# machnguon.net
KiCad netlist of a schematic drawn in Altium Designer
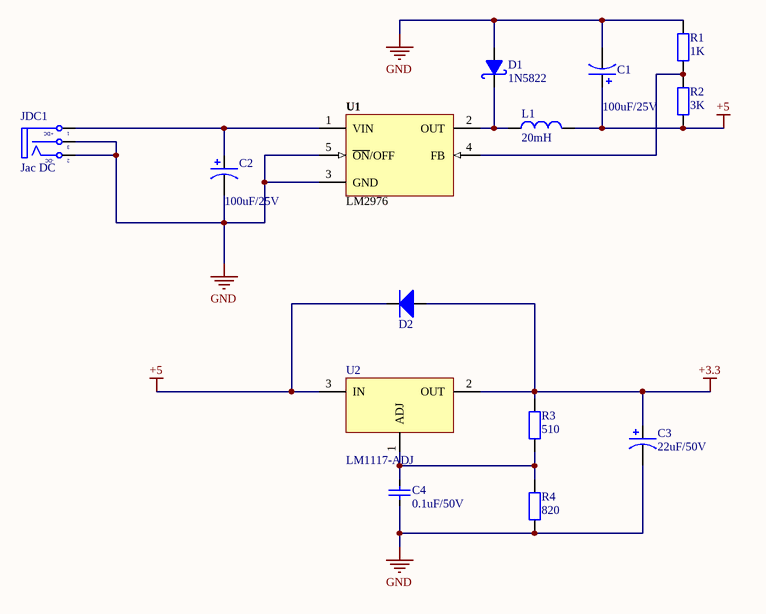
[diagram p0: machnguon.SchDoc]

(export (version "E")
  (design (tool "Eeschema 10.0.6"))
  (components
    (comp (ref "C1")
      (value "100uF/25V")
      (footprint "C3MM")
      (description "Polarized Capacitor (Axial)")
      (fields (field (name "PUBLISHER") "Altium Limited"))
      (libsource (lib "My Library") (part "Cap Pol"))
    )
    (comp (ref "C2")
      (value "100uF/25V")
      (footprint "C3MM")
      (description "Polarized Capacitor (Axial)")
      (fields (field (name "PUBLISHER") "Altium Limited"))
      (libsource (lib "My Library") (part "Cap Pol"))
    )
    (comp (ref "C3")
      (value "22uF/50V")
      (footprint "C3MM")
      (description "Polarized Capacitor (Axial)")
      (fields (field (name "PUBLISHER") "Altium Limited"))
      (libsource (lib "My Library") (part "Cap Pol"))
    )
    (comp (ref "C4")
      (value "0.1uF/50V")
      (footprint "CAP_0805")
      (description "Capacitor")
      (fields (field (name "PUBLISHER") "Altium Limited"))
      (libsource (lib "My Library") (part "CapSMD"))
    )
    (comp (ref "D1")
      (value "1N5822")
      (footprint "SMA")
      (description "Schottky Rectifiers")
      (libsource (lib "My Library") (part "1N5822"))
    )
    (comp (ref "D2")
      (value "Diode SMD")
      (footprint "DIO-SMD-106")
      (description "Default Diode")
      (fields (field (name "PUBLISHER") "Altium Limited"))
      (libsource (lib "My Library") (part "Diode SMD"))
    )
    (comp (ref "JDC1")
      (value "Jac DC")
      (footprint "DC-IN")
      (description "Jac DC input")
      (libsource (lib "My Library") (part "DCIN"))
    )
    (comp (ref "L1")
      (value "20mH")
      (footprint "L-SMD-M-7.3x4.5")
      (description "Inductor")
      (libsource (lib "My Library") (part "Inductor"))
    )
    (comp (ref "R1")
      (value "1K")
      (footprint "RES-SMD-0805")
      (description "Resistor SMD")
      (fields
        (field (name "MANUFACTURER") "Generic Components")
        (field (name "PUBLISHER") "Altium Hobart Technology Centre")
      )
      (libsource (lib "My Library") (part "Resistor - SMD"))
    )
    (comp (ref "R2")
      (value "3K")
      (footprint "RES-SMD-0805")
      (description "Resistor SMD")
      (fields
        (field (name "MANUFACTURER") "Generic Components")
        (field (name "PUBLISHER") "Altium Hobart Technology Centre")
      )
      (libsource (lib "My Library") (part "Resistor - SMD"))
    )
    (comp (ref "R3")
      (value "510")
      (footprint "RES-SMD-0805")
      (description "Resistor SMD")
      (fields
        (field (name "MANUFACTURER") "Generic Components")
        (field (name "PUBLISHER") "Altium Hobart Technology Centre")
      )
      (libsource (lib "My Library") (part "Resistor - SMD"))
    )
    (comp (ref "R4")
      (value "820")
      (footprint "RES-SMD-0805")
      (description "Resistor SMD")
      (fields
        (field (name "MANUFACTURER") "Generic Components")
        (field (name "PUBLISHER") "Altium Hobart Technology Centre")
      )
      (libsource (lib "My Library") (part "Resistor - SMD"))
    )
    (comp (ref "U1") (value "LM2976") (footprint "TO263") (libsource (lib "My Library") (part "LM2596")))
    (comp (ref "U2")
      (value "LM1117-ADJ")
      (footprint "LM1117-SOP")
      (description "800mA Low-Dropout Linear Regulator")
      (fields (field (name "CREATOR") "Nguyen Ba Bien"))
      (libsource (lib "My Library") (part "LM1117-ADJ"))
    )
  )
  (nets
    (net (code "1") (name "+3.3") (class "Default")
      (node (ref "C3") (pin "1") (pinfunction "1_1") (pintype "passive"))
      (node (ref "D2") (pin "1") (pinfunction "A_1") (pintype "passive"))
      (node (ref "R3") (pin "1") (pinfunction "1_1") (pintype "passive"))
      (node (ref "U2") (pin "2") (pinfunction "OUT_2") (pintype "passive"))
    )
    (net (code "2") (name "+5") (class "Default")
      (node (ref "C1") (pin "1") (pinfunction "1_1") (pintype "passive"))
      (node (ref "D2") (pin "2") (pinfunction "K_2") (pintype "passive"))
      (node (ref "L1") (pin "2") (pinfunction "2_2") (pintype "passive"))
      (node (ref "R2") (pin "2") (pinfunction "2_2") (pintype "passive"))
      (node (ref "U2") (pin "3") (pinfunction "IN_3") (pintype "passive"))
    )
    (net (code "3") (name "GND") (class "Default")
      (node (ref "C1") (pin "2") (pinfunction "2_2") (pintype "passive"))
      (node (ref "C2") (pin "2") (pinfunction "2_2") (pintype "passive"))
      (node (ref "C3") (pin "2") (pinfunction "2_2") (pintype "passive"))
      (node (ref "C4") (pin "1") (pinfunction "1_1") (pintype "passive"))
      (node (ref "D1") (pin "1") (pinfunction "A_1") (pintype "passive"))
      (node (ref "JDC1") (pin "2") (pinfunction "TN_2") (pintype "passive"))
      (node (ref "JDC1") (pin "3") (pinfunction "S_3") (pintype "power_in"))
      (node (ref "R1") (pin "1") (pinfunction "1_1") (pintype "passive"))
      (node (ref "R4") (pin "2") (pinfunction "2_2") (pintype "passive"))
      (node (ref "U1") (pin "3") (pinfunction "GND_3") (pintype "power_in"))
      (node (ref "U1") (pin "5") (pinfunction "~{ON}/OFF_5") (pintype "input"))
    )
    (net (code "4") (name "Net-(D1-K)") (class "Default")
      (node (ref "D1") (pin "2") (pinfunction "K_2") (pintype "passive"))
      (node (ref "L1") (pin "1") (pinfunction "1_1") (pintype "passive"))
      (node (ref "U1") (pin "2") (pinfunction "OUT_2") (pintype "power_in"))
    )
    (net (code "5") (name "Net-(JDC1-T)") (class "Default")
      (node (ref "C2") (pin "1") (pinfunction "1_1") (pintype "passive"))
      (node (ref "JDC1") (pin "1") (pinfunction "T_1") (pintype "passive"))
      (node (ref "U1") (pin "1") (pinfunction "VIN_1") (pintype "power_in"))
    )
    (net (code "6") (name "Net-(U1-FB)") (class "Default")
      (node (ref "R1") (pin "2") (pinfunction "2_2") (pintype "passive"))
      (node (ref "R2") (pin "1") (pinfunction "1_1") (pintype "passive"))
      (node (ref "U1") (pin "4") (pinfunction "FB_4") (pintype "input"))
    )
    (net (code "7") (name "Net-(U2-ADJ)") (class "Default")
      (node (ref "C4") (pin "2") (pinfunction "2_2") (pintype "passive"))
      (node (ref "R3") (pin "2") (pinfunction "2_2") (pintype "passive"))
      (node (ref "R4") (pin "1") (pinfunction "1_1") (pintype "passive"))
      (node (ref "U2") (pin "1") (pinfunction "ADJ_1") (pintype "passive"))
    )
  )
)
